# Escon_backboard.net
KiCad netlist of a schematic drawn in EAGLE
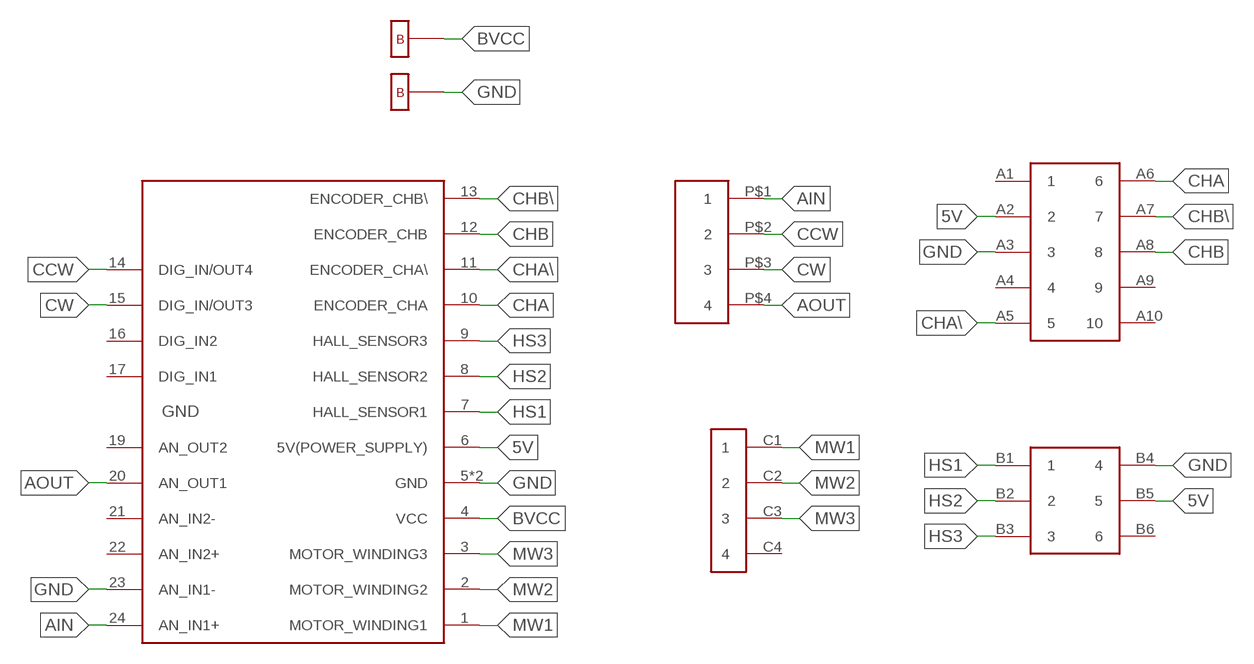
[diagram p0: schematic, sheet 1]

(export (version "E")
  (design (tool "Eeschema 10.0.6"))
  (components
    (comp (ref "U$1")
      (value "ESCON24/224/2")
      (footprint "eagle-import:ESCON24_2")
      (libsource (lib "eagle-import") (part "ESCON24/224/2"))
    )
    (comp (ref "U$2")
      (value "280378-2CONNECTOR")
      (footprint "eagle-import:280378-2CONNECTOR")
      (libsource (lib "eagle-import") (part "280378-2CONNECTOR"))
    )
    (comp (ref "U$3")
      (value "PIN2.54-2X5")
      (footprint "eagle-import:PIN2.54-2X5")
      (libsource (lib "eagle-import") (part "PIN2.54-2X5"))
    )
    (comp (ref "U$4")
      (value "MX-44914-0601")
      (footprint "eagle-import:MX-44914-0601")
      (libsource (lib "eagle-import") (part "MX-44914-0601"))
    )
    (comp (ref "U$5")
      (value "MX5566")
      (footprint "eagle-import:MX5566")
      (libsource (lib "eagle-import") (part "MX5566"))
    )
    (comp (ref "U$6")
      (value "BHOLE")
      (footprint "eagle-import:BHOLE")
      (libsource (lib "eagle-import") (part "BHOLE"))
    )
    (comp (ref "U$7")
      (value "BHOLE")
      (footprint "eagle-import:BHOLE")
      (libsource (lib "eagle-import") (part "BHOLE"))
    )
  )
  (nets
    (net (code "1") (name "5V") (class "Default")
      (node (ref "U$1") (pin "6") (pinfunction "5V(POWER_SUPPLY)_6") (pintype "bidirectional"))
      (node (ref "U$3") (pin "A2") (pinfunction "2_A2") (pintype "bidirectional"))
      (node (ref "U$4") (pin "B5") (pinfunction "5_B5") (pintype "bidirectional"))
    )
    (net (code "2") (name "AIN") (class "Default")
      (node (ref "U$1") (pin "24") (pinfunction "AN_IN1+_24") (pintype "bidirectional"))
      (node (ref "U$2") (pin "P$1") (pinfunction "1_P$1") (pintype "bidirectional"))
    )
    (net (code "3") (name "AOUT") (class "Default")
      (node (ref "U$1") (pin "20") (pinfunction "AN_OUT1_20") (pintype "bidirectional"))
      (node (ref "U$2") (pin "P$4") (pinfunction "4_P$4") (pintype "bidirectional"))
    )
    (net (code "4") (name "BVCC") (class "Default")
      (node (ref "U$1") (pin "4") (pinfunction "VCC_4") (pintype "bidirectional"))
      (node (ref "U$6") (pin "P$1") (pinfunction "P$1_P$1") (pintype "bidirectional"))
    )
    (net (code "5") (name "CCW") (class "Default")
      (node (ref "U$1") (pin "14") (pinfunction "DIG_IN/OUT4_14") (pintype "bidirectional"))
      (node (ref "U$2") (pin "P$2") (pinfunction "2_P$2") (pintype "bidirectional"))
    )
    (net (code "6") (name "CHA") (class "Default")
      (node (ref "U$1") (pin "10") (pinfunction "ENCODER_CHA_10") (pintype "bidirectional"))
      (node (ref "U$3") (pin "A6") (pinfunction "6_A6") (pintype "bidirectional"))
    )
    (net (code "7") (name "CHA\\\\") (class "Default")
      (node (ref "U$1") (pin "11") (pinfunction "ENCODER_CHA\\\\_11") (pintype "bidirectional"))
      (node (ref "U$3") (pin "A5") (pinfunction "5_A5") (pintype "bidirectional"))
    )
    (net (code "8") (name "CHB") (class "Default")
      (node (ref "U$1") (pin "12") (pinfunction "ENCODER_CHB_12") (pintype "bidirectional"))
      (node (ref "U$3") (pin "A8") (pinfunction "8_A8") (pintype "bidirectional"))
    )
    (net (code "9") (name "CHB\\\\") (class "Default")
      (node (ref "U$1") (pin "13") (pinfunction "ENCODER_CHB\\\\_13") (pintype "bidirectional"))
      (node (ref "U$3") (pin "A7") (pinfunction "7_A7") (pintype "bidirectional"))
    )
    (net (code "10") (name "CW") (class "Default")
      (node (ref "U$1") (pin "15") (pinfunction "DIG_IN/OUT3_15") (pintype "bidirectional"))
      (node (ref "U$2") (pin "P$3") (pinfunction "3_P$3") (pintype "bidirectional"))
    )
    (net (code "11") (name "GND") (class "Default")
      (node (ref "U$1") (pin "18") (pinfunction "GND_18") (pintype "bidirectional"))
      (node (ref "U$1") (pin "23") (pinfunction "AN_IN1-_23") (pintype "bidirectional"))
      (node (ref "U$1") (pin "5") (pinfunction "GND_5") (pintype "bidirectional"))
      (node (ref "U$3") (pin "A3") (pinfunction "3_A3") (pintype "bidirectional"))
      (node (ref "U$4") (pin "B4") (pinfunction "4_B4") (pintype "bidirectional"))
      (node (ref "U$7") (pin "P$1") (pinfunction "P$1_P$1") (pintype "bidirectional"))
    )
    (net (code "12") (name "HS1") (class "Default")
      (node (ref "U$1") (pin "7") (pinfunction "HALL_SENSOR1_7") (pintype "bidirectional"))
      (node (ref "U$4") (pin "B1") (pinfunction "1_B1") (pintype "bidirectional"))
    )
    (net (code "13") (name "HS2") (class "Default")
      (node (ref "U$1") (pin "8") (pinfunction "HALL_SENSOR2_8") (pintype "bidirectional"))
      (node (ref "U$4") (pin "B2") (pinfunction "2_B2") (pintype "bidirectional"))
    )
    (net (code "14") (name "HS3") (class "Default")
      (node (ref "U$1") (pin "9") (pinfunction "HALL_SENSOR3_9") (pintype "bidirectional"))
      (node (ref "U$4") (pin "B3") (pinfunction "3_B3") (pintype "bidirectional"))
    )
    (net (code "15") (name "MW1") (class "Default")
      (node (ref "U$1") (pin "1") (pinfunction "MOTOR_WINDING1_1") (pintype "bidirectional"))
      (node (ref "U$5") (pin "C1") (pinfunction "1_C1") (pintype "bidirectional"))
    )
    (net (code "16") (name "MW2") (class "Default")
      (node (ref "U$1") (pin "2") (pinfunction "MOTOR_WINDING2_2") (pintype "bidirectional"))
      (node (ref "U$5") (pin "C2") (pinfunction "2_C2") (pintype "bidirectional"))
    )
    (net (code "17") (name "MW3") (class "Default")
      (node (ref "U$1") (pin "3") (pinfunction "MOTOR_WINDING3_3") (pintype "bidirectional"))
      (node (ref "U$5") (pin "C3") (pinfunction "3_C3") (pintype "bidirectional"))
    )
    (net (code "18") (name "unconnected-(U$1-AN_IN2+-Pad22)") (class "Default")
      (node (ref "U$1") (pin "22") (pinfunction "AN_IN2+_22") (pintype "bidirectional"))
    )
    (net (code "19") (name "unconnected-(U$1-AN_IN2--Pad21)") (class "Default")
      (node (ref "U$1") (pin "21") (pinfunction "AN_IN2-_21") (pintype "bidirectional"))
    )
    (net (code "20") (name "unconnected-(U$1-AN_OUT2-Pad19)") (class "Default")
      (node (ref "U$1") (pin "19") (pinfunction "AN_OUT2_19") (pintype "bidirectional"))
    )
    (net (code "21") (name "unconnected-(U$1-DIG_IN1-Pad17)") (class "Default")
      (node (ref "U$1") (pin "17") (pinfunction "DIG_IN1_17") (pintype "bidirectional"))
    )
    (net (code "22") (name "unconnected-(U$1-DIG_IN2-Pad16)") (class "Default")
      (node (ref "U$1") (pin "16") (pinfunction "DIG_IN2_16") (pintype "bidirectional"))
    )
    (net (code "23") (name "unconnected-(U$3-1-PadA1)") (class "Default")
      (node (ref "U$3") (pin "A1") (pinfunction "1_A1") (pintype "bidirectional"))
    )
    (net (code "24") (name "unconnected-(U$3-4-PadA4)") (class "Default")
      (node (ref "U$3") (pin "A4") (pinfunction "4_A4") (pintype "bidirectional"))
    )
    (net (code "25") (name "unconnected-(U$3-9-PadA9)") (class "Default")
      (node (ref "U$3") (pin "A9") (pinfunction "9_A9") (pintype "bidirectional"))
    )
    (net (code "26") (name "unconnected-(U$3-10-PadA10)") (class "Default")
      (node (ref "U$3") (pin "A10") (pinfunction "10_A10") (pintype "bidirectional"))
    )
    (net (code "27") (name "unconnected-(U$4-6-PadB6)") (class "Default")
      (node (ref "U$4") (pin "B6") (pinfunction "6_B6") (pintype "bidirectional"))
    )
    (net (code "28") (name "unconnected-(U$5-4-PadC4)") (class "Default")
      (node (ref "U$5") (pin "C4") (pinfunction "4_C4") (pintype "bidirectional"))
    )
  )
)
